# NEPconn.net
KiCad netlist of a schematic drawn in Altium Designer
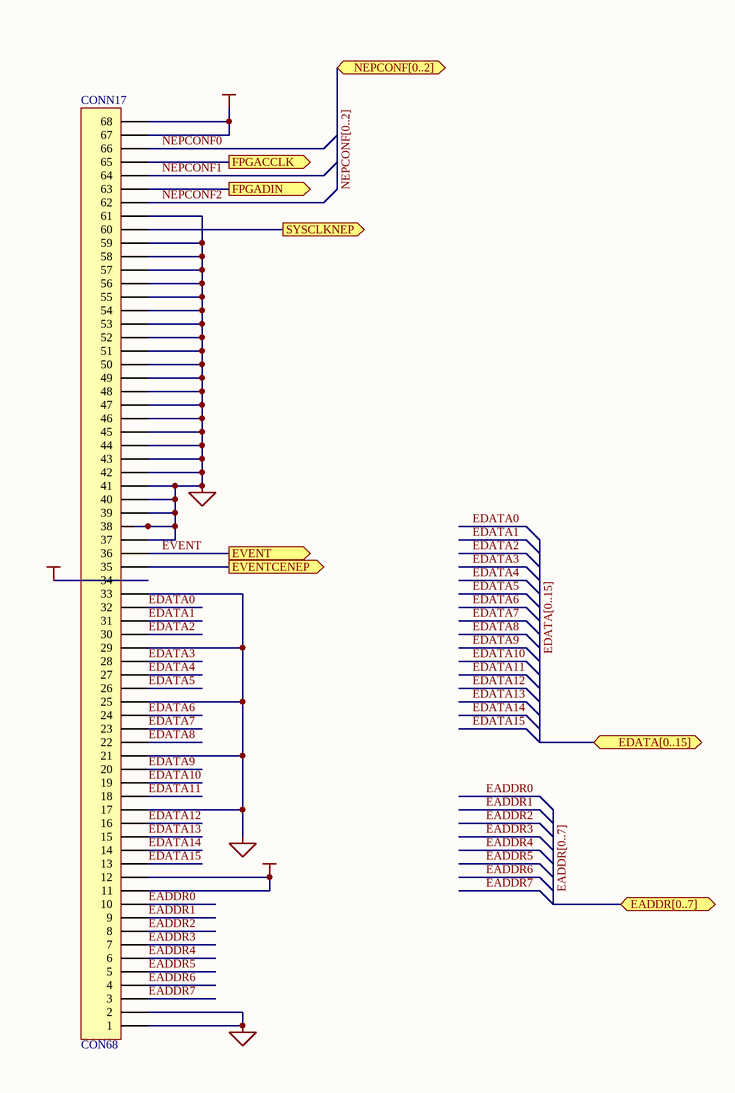
[diagram p0: NEPconn.SCHDOC]

(export (version "E")
  (design (tool "Eeschema 10.0.6"))
  (components
    (comp (ref "CONN17")
      (value "CON68")
      (footprint "MOLEX 15921068")
      (libsource (lib "My devices") (part "CON68"))
    )
  )
  (nets
    (net (code "1") (name "+5VCC") (class "Default")
      (node (ref "CONN17") (pin "34") (pinfunction "34_34") (pintype "passive"))
    )
    (net (code "2") (name "/EADDR0") (class "Default")
      (node (ref "CONN17") (pin "10") (pinfunction "10_10") (pintype "passive"))
    )
    (net (code "3") (name "/EADDR1") (class "Default")
      (node (ref "CONN17") (pin "9") (pinfunction "9_9") (pintype "passive"))
    )
    (net (code "4") (name "/EADDR2") (class "Default")
      (node (ref "CONN17") (pin "8") (pinfunction "8_8") (pintype "passive"))
    )
    (net (code "5") (name "/EADDR3") (class "Default")
      (node (ref "CONN17") (pin "7") (pinfunction "7_7") (pintype "passive"))
    )
    (net (code "6") (name "/EADDR4") (class "Default")
      (node (ref "CONN17") (pin "6") (pinfunction "6_6") (pintype "passive"))
    )
    (net (code "7") (name "/EADDR5") (class "Default")
      (node (ref "CONN17") (pin "5") (pinfunction "5_5") (pintype "passive"))
    )
    (net (code "8") (name "/EADDR6") (class "Default")
      (node (ref "CONN17") (pin "4") (pinfunction "4_4") (pintype "passive"))
    )
    (net (code "9") (name "/EADDR7") (class "Default")
      (node (ref "CONN17") (pin "3") (pinfunction "3_3") (pintype "passive"))
    )
    (net (code "11") (name "/EDATA0") (class "Default")
      (node (ref "CONN17") (pin "32") (pinfunction "32_32") (pintype "passive"))
    )
    (net (code "12") (name "/EDATA1") (class "Default")
      (node (ref "CONN17") (pin "31") (pinfunction "31_31") (pintype "passive"))
    )
    (net (code "13") (name "/EDATA2") (class "Default")
      (node (ref "CONN17") (pin "30") (pinfunction "30_30") (pintype "passive"))
    )
    (net (code "14") (name "/EDATA3") (class "Default")
      (node (ref "CONN17") (pin "28") (pinfunction "28_28") (pintype "passive"))
    )
    (net (code "15") (name "/EDATA4") (class "Default")
      (node (ref "CONN17") (pin "27") (pinfunction "27_27") (pintype "passive"))
    )
    (net (code "16") (name "/EDATA5") (class "Default")
      (node (ref "CONN17") (pin "26") (pinfunction "26_26") (pintype "passive"))
    )
    (net (code "17") (name "/EDATA6") (class "Default")
      (node (ref "CONN17") (pin "24") (pinfunction "24_24") (pintype "passive"))
    )
    (net (code "18") (name "/EDATA7") (class "Default")
      (node (ref "CONN17") (pin "23") (pinfunction "23_23") (pintype "passive"))
    )
    (net (code "19") (name "/EDATA8") (class "Default")
      (node (ref "CONN17") (pin "22") (pinfunction "22_22") (pintype "passive"))
    )
    (net (code "20") (name "/EDATA9") (class "Default")
      (node (ref "CONN17") (pin "20") (pinfunction "20_20") (pintype "passive"))
    )
    (net (code "21") (name "/EDATA10") (class "Default")
      (node (ref "CONN17") (pin "19") (pinfunction "19_19") (pintype "passive"))
    )
    (net (code "22") (name "/EDATA11") (class "Default")
      (node (ref "CONN17") (pin "18") (pinfunction "18_18") (pintype "passive"))
    )
    (net (code "23") (name "/EDATA12") (class "Default")
      (node (ref "CONN17") (pin "16") (pinfunction "16_16") (pintype "passive"))
    )
    (net (code "24") (name "/EDATA13") (class "Default")
      (node (ref "CONN17") (pin "15") (pinfunction "15_15") (pintype "passive"))
    )
    (net (code "25") (name "/EDATA14") (class "Default")
      (node (ref "CONN17") (pin "14") (pinfunction "14_14") (pintype "passive"))
    )
    (net (code "26") (name "/EDATA15") (class "Default")
      (node (ref "CONN17") (pin "13") (pinfunction "13_13") (pintype "passive"))
    )
    (net (code "28") (name "/EVENT") (class "Default")
      (node (ref "CONN17") (pin "36") (pinfunction "36_36") (pintype "passive"))
    )
    (net (code "29") (name "/EVENTCENEP") (class "Default")
      (node (ref "CONN17") (pin "35") (pinfunction "35_35") (pintype "passive"))
    )
    (net (code "30") (name "/FPGACCLK") (class "Default")
      (node (ref "CONN17") (pin "65") (pinfunction "65_65") (pintype "passive"))
    )
    (net (code "31") (name "/FPGADIN") (class "Default")
      (node (ref "CONN17") (pin "63") (pinfunction "63_63") (pintype "passive"))
    )
    (net (code "32") (name "/NEPCONF0") (class "Default")
      (node (ref "CONN17") (pin "66") (pinfunction "66_66") (pintype "passive"))
    )
    (net (code "33") (name "/NEPCONF1") (class "Default")
      (node (ref "CONN17") (pin "64") (pinfunction "64_64") (pintype "passive"))
    )
    (net (code "34") (name "/NEPCONF2") (class "Default")
      (node (ref "CONN17") (pin "62") (pinfunction "62_62") (pintype "passive"))
    )
    (net (code "36") (name "/SYSCLKNEP") (class "Default")
      (node (ref "CONN17") (pin "60") (pinfunction "60_60") (pintype "passive"))
    )
    (net (code "37") (name "GND") (class "Default")
      (node (ref "CONN17") (pin "1") (pinfunction "1_1") (pintype "passive"))
      (node (ref "CONN17") (pin "17") (pinfunction "17_17") (pintype "passive"))
      (node (ref "CONN17") (pin "2") (pinfunction "2_2") (pintype "passive"))
      (node (ref "CONN17") (pin "21") (pinfunction "21_21") (pintype "passive"))
      (node (ref "CONN17") (pin "25") (pinfunction "25_25") (pintype "passive"))
      (node (ref "CONN17") (pin "29") (pinfunction "29_29") (pintype "passive"))
      (node (ref "CONN17") (pin "33") (pinfunction "33_33") (pintype "passive"))
      (node (ref "CONN17") (pin "37") (pinfunction "37_37") (pintype "passive"))
      (node (ref "CONN17") (pin "38") (pinfunction "38_38") (pintype "passive"))
      (node (ref "CONN17") (pin "39") (pinfunction "39_39") (pintype "passive"))
      (node (ref "CONN17") (pin "40") (pinfunction "40_40") (pintype "passive"))
      (node (ref "CONN17") (pin "41") (pinfunction "41_41") (pintype "passive"))
      (node (ref "CONN17") (pin "42") (pinfunction "42_42") (pintype "passive"))
      (node (ref "CONN17") (pin "43") (pinfunction "43_43") (pintype "passive"))
      (node (ref "CONN17") (pin "44") (pinfunction "44_44") (pintype "passive"))
      (node (ref "CONN17") (pin "45") (pinfunction "45_45") (pintype "passive"))
      (node (ref "CONN17") (pin "46") (pinfunction "46_46") (pintype "passive"))
      (node (ref "CONN17") (pin "47") (pinfunction "47_47") (pintype "passive"))
      (node (ref "CONN17") (pin "48") (pinfunction "48_48") (pintype "passive"))
      (node (ref "CONN17") (pin "49") (pinfunction "49_49") (pintype "passive"))
      (node (ref "CONN17") (pin "50") (pinfunction "50_50") (pintype "passive"))
      (node (ref "CONN17") (pin "51") (pinfunction "51_51") (pintype "passive"))
      (node (ref "CONN17") (pin "52") (pinfunction "52_52") (pintype "passive"))
      (node (ref "CONN17") (pin "53") (pinfunction "53_53") (pintype "passive"))
      (node (ref "CONN17") (pin "54") (pinfunction "54_54") (pintype "passive"))
      (node (ref "CONN17") (pin "55") (pinfunction "55_55") (pintype "passive"))
      (node (ref "CONN17") (pin "56") (pinfunction "56_56") (pintype "passive"))
      (node (ref "CONN17") (pin "57") (pinfunction "57_57") (pintype "passive"))
      (node (ref "CONN17") (pin "58") (pinfunction "58_58") (pintype "passive"))
      (node (ref "CONN17") (pin "59") (pinfunction "59_59") (pintype "passive"))
      (node (ref "CONN17") (pin "61") (pinfunction "61_61") (pintype "passive"))
    )
    (net (code "38") (name "VCC") (class "Default")
      (node (ref "CONN17") (pin "11") (pinfunction "11_11") (pintype "passive"))
      (node (ref "CONN17") (pin "12") (pinfunction "12_12") (pintype "passive"))
      (node (ref "CONN17") (pin "67") (pinfunction "67_67") (pintype "passive"))
      (node (ref "CONN17") (pin "68") (pinfunction "68_68") (pintype "passive"))
    )
  )
)
